# auido.net
KiCad netlist of a schematic drawn in Altium Designer
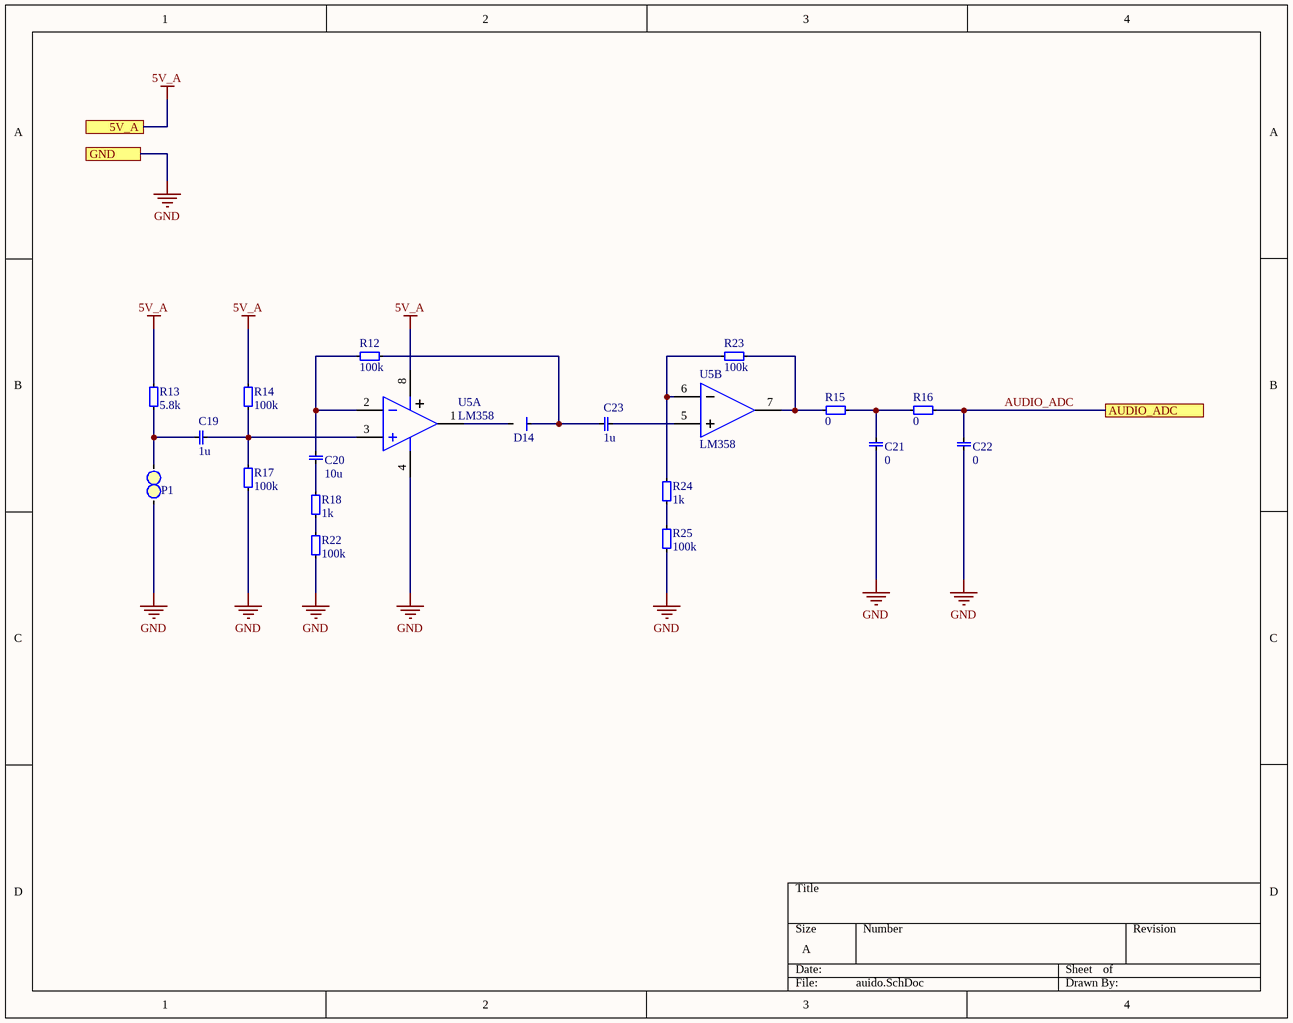
[diagram p0: auido.SchDoc]

(export (version "E")
  (design (tool "Eeschema 10.0.6"))
  (components
    (comp (ref "C19")
      (value "1u")
      (footprint "0603 cap")
      (fields (field (name "Comment") "0603, capacitor"))
      (libsource (lib "jclib") (part "0603, capacitor"))
    )
    (comp (ref "C20")
      (value "10u")
      (footprint "0603 cap")
      (fields (field (name "Comment") "0603, capacitor"))
      (libsource (lib "jclib") (part "0603, capacitor"))
    )
    (comp (ref "C21")
      (value "0")
      (footprint "0603 cap")
      (fields (field (name "Comment") "0603, capacitor"))
      (libsource (lib "jclib") (part "0603, capacitor"))
    )
    (comp (ref "C22")
      (value "0")
      (footprint "0603 cap")
      (fields (field (name "Comment") "0603, capacitor"))
      (libsource (lib "jclib") (part "0603, capacitor"))
    )
    (comp (ref "C23")
      (value "1u")
      (footprint "0603 cap")
      (fields (field (name "Comment") "0603, capacitor"))
      (libsource (lib "jclib") (part "0603, capacitor"))
    )
    (comp (ref "D14") (value "Diode, SMD") (footprint "SOD323") (libsource (lib "jclib") (part "Diode, SMD")))
    (comp (ref "P1")
      (value "1x2 Pin Heade Straight")
      (footprint "padtwo_L")
      (description "2.54 mm, TH")
      (libsource (lib "jclib") (part "1x2 Pin Heade Straight"))
    )
    (comp (ref "R12")
      (value "100k")
      (footprint "0603")
      (fields (field (name "Comment") "0603, resistor"))
      (libsource (lib "jclib") (part "0603, resistor"))
    )
    (comp (ref "R13")
      (value "5.8k")
      (footprint "0603")
      (fields (field (name "Comment") "0603, resistor"))
      (libsource (lib "jclib") (part "0603, resistor"))
    )
    (comp (ref "R14")
      (value "100k")
      (footprint "0603")
      (fields (field (name "Comment") "0603, resistor"))
      (libsource (lib "jclib") (part "0603, resistor"))
    )
    (comp (ref "R15")
      (value "0")
      (footprint "0603")
      (fields (field (name "Comment") "0603, resistor"))
      (libsource (lib "jclib") (part "0603, resistor"))
    )
    (comp (ref "R16")
      (value "0")
      (footprint "0603")
      (fields (field (name "Comment") "0603, resistor"))
      (libsource (lib "jclib") (part "0603, resistor"))
    )
    (comp (ref "R17")
      (value "100k")
      (footprint "0603")
      (fields (field (name "Comment") "0603, resistor"))
      (libsource (lib "jclib") (part "0603, resistor"))
    )
    (comp (ref "R18")
      (value "1k")
      (footprint "0603")
      (fields (field (name "Comment") "0603, resistor"))
      (libsource (lib "jclib") (part "0603, resistor"))
    )
    (comp (ref "R22")
      (value "100k")
      (footprint "0603")
      (fields (field (name "Comment") "0603, resistor"))
      (libsource (lib "jclib") (part "0603, resistor"))
    )
    (comp (ref "R23")
      (value "100k")
      (footprint "0603")
      (fields (field (name "Comment") "0603, resistor"))
      (libsource (lib "jclib") (part "0603, resistor"))
    )
    (comp (ref "R24")
      (value "1k")
      (footprint "0603")
      (fields (field (name "Comment") "0603, resistor"))
      (libsource (lib "jclib") (part "0603, resistor"))
    )
    (comp (ref "R25")
      (value "100k")
      (footprint "0603")
      (fields (field (name "Comment") "0603, resistor"))
      (libsource (lib "jclib") (part "0603, resistor"))
    )
    (comp (ref "U5")
      (value "LM358")
      (footprint "SOIC8")
      (description "Dual FET-Input Operational Amplifier")
      (fields (field (name "PART NUMBER") "LM358P"))
      (libsource (lib "jclib") (part "LM358"))
    )
  )
  (nets
    (net (code "1") (name "/AUDIO_ADC") (class "Default")
      (node (ref "C22") (pin "1") (pinfunction "1_1") (pintype "passive"))
      (node (ref "R16") (pin "1") (pinfunction "1_1") (pintype "passive"))
    )
    (net (code "2") (name "5V_A") (class "Default")
      (node (ref "R13") (pin "0") (pinfunction "0_0") (pintype "passive"))
      (node (ref "R14") (pin "0") (pinfunction "0_0") (pintype "passive"))
      (node (ref "U5") (pin "8") (pinfunction "V+_8") (pintype "power_in"))
    )
    (net (code "3") (name "GND") (class "Default")
      (node (ref "C21") (pin "0") (pinfunction "0_0") (pintype "passive"))
      (node (ref "C22") (pin "0") (pinfunction "0_0") (pintype "passive"))
      (node (ref "P1") (pin "2") (pinfunction "2_2") (pintype "passive"))
      (node (ref "R17") (pin "1") (pinfunction "1_1") (pintype "passive"))
      (node (ref "R22") (pin "1") (pinfunction "1_1") (pintype "passive"))
      (node (ref "R25") (pin "1") (pinfunction "1_1") (pintype "passive"))
      (node (ref "U5") (pin "4") (pinfunction "V-_4") (pintype "power_in"))
    )
    (net (code "4") (name "Net-(C19-Pad1)") (class "Default")
      (node (ref "C19") (pin "1") (pinfunction "1_1") (pintype "passive"))
      (node (ref "P1") (pin "1") (pinfunction "1_1") (pintype "passive"))
      (node (ref "R13") (pin "1") (pinfunction "1_1") (pintype "passive"))
    )
    (net (code "5") (name "Net-(C20-Pad0)") (class "Default")
      (node (ref "C20") (pin "0") (pinfunction "0_0") (pintype "passive"))
      (node (ref "R18") (pin "0") (pinfunction "0_0") (pintype "passive"))
    )
    (net (code "6") (name "Net-(C21-Pad1)") (class "Default")
      (node (ref "C21") (pin "1") (pinfunction "1_1") (pintype "passive"))
      (node (ref "R15") (pin "1") (pinfunction "1_1") (pintype "passive"))
      (node (ref "R16") (pin "0") (pinfunction "0_0") (pintype "passive"))
    )
    (net (code "7") (name "Net-(C23-Pad1)") (class "Default")
      (node (ref "C23") (pin "1") (pinfunction "1_1") (pintype "passive"))
      (node (ref "D14") (pin "1") (pinfunction "1_1") (pintype "passive"))
      (node (ref "R12") (pin "1") (pinfunction "1_1") (pintype "passive"))
    )
    (net (code "8") (name "Net-(R18-Pad1)") (class "Default")
      (node (ref "R18") (pin "1") (pinfunction "1_1") (pintype "passive"))
      (node (ref "R22") (pin "0") (pinfunction "0_0") (pintype "passive"))
    )
    (net (code "9") (name "Net-(R24-Pad1)") (class "Default")
      (node (ref "R24") (pin "1") (pinfunction "1_1") (pintype "passive"))
      (node (ref "R25") (pin "0") (pinfunction "0_0") (pintype "passive"))
    )
    (net (code "10") (name "Net-(U5A-IN+)") (class "Default")
      (node (ref "C19") (pin "0") (pinfunction "0_0") (pintype "passive"))
      (node (ref "R14") (pin "1") (pinfunction "1_1") (pintype "passive"))
      (node (ref "R17") (pin "0") (pinfunction "0_0") (pintype "passive"))
      (node (ref "U5") (pin "3") (pinfunction "IN+_3") (pintype "passive"))
    )
    (net (code "11") (name "Net-(U5A-IN-)") (class "Default")
      (node (ref "C20") (pin "1") (pinfunction "1_1") (pintype "passive"))
      (node (ref "R12") (pin "0") (pinfunction "0_0") (pintype "passive"))
      (node (ref "U5") (pin "2") (pinfunction "IN-_2") (pintype "passive"))
    )
    (net (code "12") (name "Net-(U5A-OUT1)") (class "Default")
      (node (ref "D14") (pin "2") (pinfunction "2_2") (pintype "passive"))
      (node (ref "U5") (pin "1") (pinfunction "OUT1_1") (pintype "passive"))
    )
    (net (code "13") (name "Net-(U5B-IN+)") (class "Default")
      (node (ref "C23") (pin "0") (pinfunction "0_0") (pintype "passive"))
      (node (ref "U5") (pin "5") (pinfunction "IN+_5") (pintype "passive"))
    )
    (net (code "14") (name "Net-(U5B-IN-)") (class "Default")
      (node (ref "R23") (pin "0") (pinfunction "0_0") (pintype "passive"))
      (node (ref "R24") (pin "0") (pinfunction "0_0") (pintype "passive"))
      (node (ref "U5") (pin "6") (pinfunction "IN-_6") (pintype "passive"))
    )
    (net (code "15") (name "Net-(U5B-OUT2)") (class "Default")
      (node (ref "R15") (pin "0") (pinfunction "0_0") (pintype "passive"))
      (node (ref "R23") (pin "1") (pinfunction "1_1") (pintype "passive"))
      (node (ref "U5") (pin "7") (pinfunction "OUT2_7") (pintype "passive"))
    )
  )
)
